# ESP32.net
KiCad netlist of a schematic drawn in Altium Designer
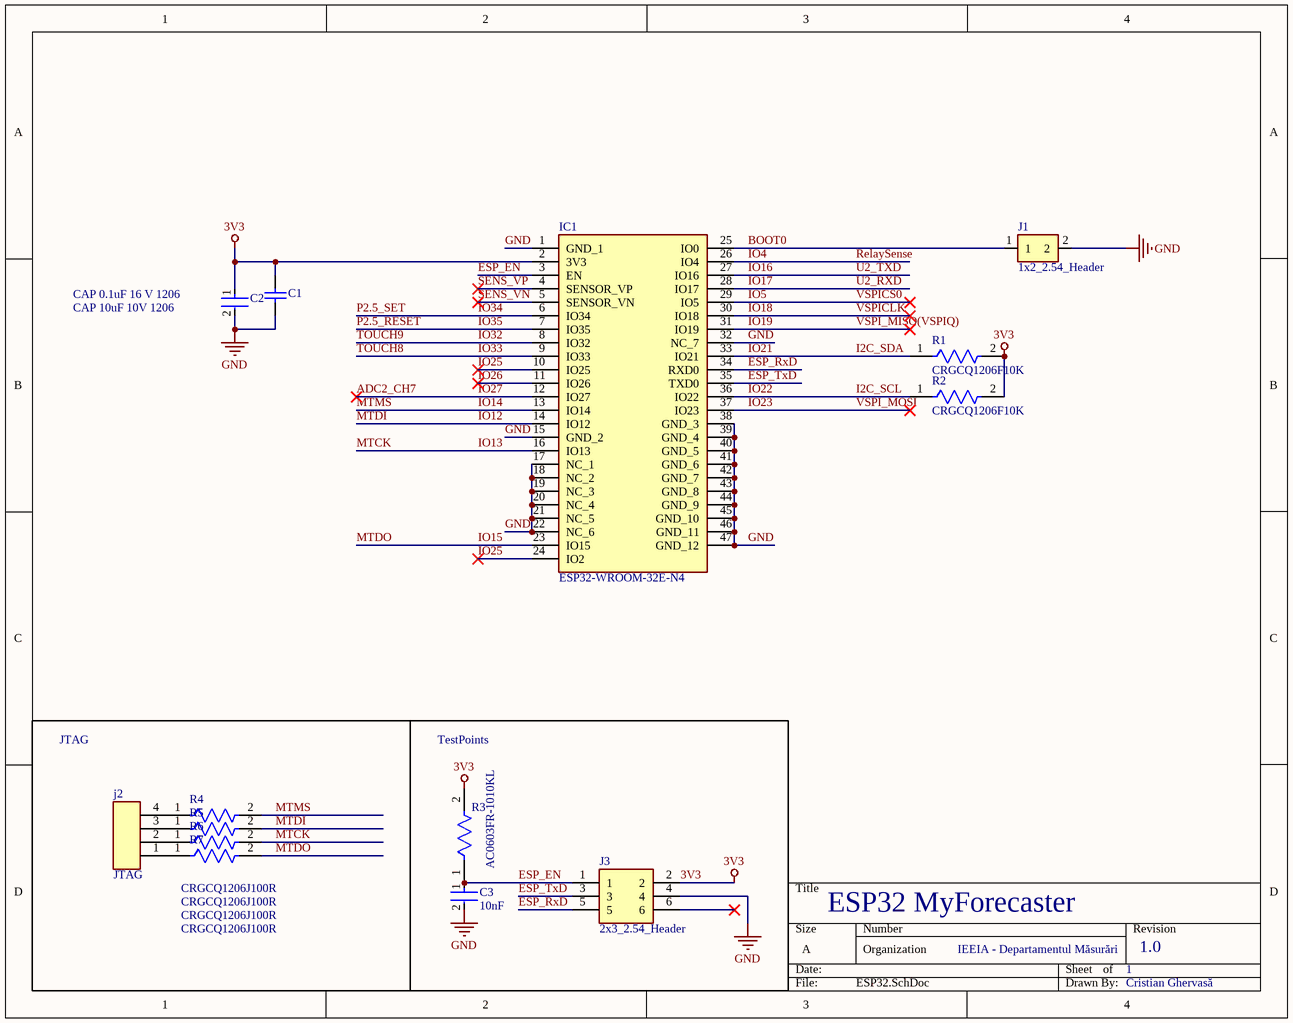
[diagram p0: ESP32.SchDoc]

(export (version "E")
  (design (tool "Eeschema 10.0.6"))
  (components
    (comp (ref "C1")
      (value "CAP 10uF 10V 1206")
      (footprint "CAPC1206(3216)190_N")
      (description "CAP 10uF 10V ±5% 1206 (3216 Metric) Thickness 1.9mm SMD")
      (fields (field (name "TOLERANCE") "Â±5%"))
      (libsource (lib "Altium Content Vault") (part "CAP"))
    )
    (comp (ref "C2")
      (value "CAP 0.1uF 16 V 1206")
      (footprint "FP-C1206C-EB-MFG")
      (description "C1206 0.10 μF X7R 10.00% 16 V")
      (fields (field (name "TOLERANCE") "0.1") (field (name "MANUFACTURER PART NUMBER") "C1206C104K4RACAUTO"))
      (libsource (lib "Altium Content Vault") (part "b4654b650e69147ec39a6b967a45e02"))
    )
    (comp (ref "C3")
      (value "10nF")
      (footprint "FP-CL10-IPC_B")
      (description "Cap Ceramic 10nF 25V X7R ±10% Pad SMD 0603 +125°C T/R")
      (fields (field (name "TOLERANCE") "10%") (field (name "VOLTAGE") "50V"))
      (libsource (lib "Altium Content Vault") (part "b4654b650e69147ec39a6b967a45e02"))
    )
    (comp (ref "IC1")
      (value "ESP32-WROOM-32E-N4")
      (footprint "SamacSys:ESP32WROOM32EN4")
      (description "Integrated Circuit")
      (fields (field (name "MOUSER PART NUMBER") "356-ESP32WRM32E132PH"))
      (libsource (lib "*") (part "ESP32-WROOM-32E-N4"))
    )
    (comp (ref "J1")
      (value "1x2_2.54_Header")
      (footprint "1x2_2.54_Header")
      (description "Connector")
      (libsource (lib "NFC_MedicalAQ") (part "1x2_2.54_Header"))
    )
    (comp (ref "j2")
      (value "JTAG")
      (footprint "1x4_2.54_Header")
      (description "Connector")
      (libsource (lib "NFC_MedicalAQ") (part "1x4_2.54_Header"))
    )
    (comp (ref "J3")
      (value "2x3_2.54_Header")
      (footprint "2x3_2.54_Header")
      (description "Connector")
      (fields
        (field (name "MANUFACTURER_PART_NUMBER") "5-146254-3")
        (field (name "MOUSER PART NUMBER") "571-5-146254-3")
      )
      (libsource (lib "NFC_MedicalAQ") (part "2x3_2.54_Header"))
    )
    (comp (ref "R1")
      (value "CRGCQ1206F10K")
      (footprint "FP-CRGCQ1206-IPC_C")
      (description "CRGCQ1206 10KΩ 0.25W 1% ±100ppm/°C 200V")
      (fields (field (name "MANUFACTURER") "TE Connectivity") (field (name "TOLERANCE") "0.01"))
      (libsource (lib "Altium Content Vault") (part "1029c3af85768c4190bb7ad29bc67b5"))
    )
    (comp (ref "R2")
      (value "CRGCQ1206F10K")
      (footprint "FP-CRGCQ1206-IPC_C")
      (description "CRGCQ1206 10KΩ 0.25W 1% ±100ppm/°C 200V")
      (fields (field (name "MANUFACTURER") "TE Connectivity") (field (name "TOLERANCE") "0.01"))
      (libsource (lib "Altium Content Vault") (part "1029c3af85768c4190bb7ad29bc67b5"))
    )
    (comp (ref "R3")
      (value "AC0603FR-1010KL")
      (footprint "FP-AC0603-IPC_B")
      (description "RES 10KΩ 1.00% 0.1W 0603")
      (fields (field (name "TOLERANCE") "1%"))
      (libsource (lib "Altium Content Vault") (part "1029c3af85768c4190bb7ad29bc67b5"))
    )
    (comp (ref "R4")
      (value "CRGCQ1206J100R")
      (footprint "FP-CRGCQ1206-IPC_C")
      (description "CRGCQ1206 100Ω 0.25W 5% ±200ppm/°C 200V")
      (fields
        (field (name "MANUFACTURER") "TE Connectivity")
        (field (name "OCTOPART") "https://octopart.com/crgcq1206j100r-te+connectivity-91018304")
      )
      (libsource (lib "Altium Content Vault") (part "1029c3af85768c4190bb7ad29bc67b5"))
    )
    (comp (ref "R5")
      (value "CRGCQ1206J100R")
      (footprint "FP-CRGCQ1206-IPC_C")
      (description "CRGCQ1206 100Ω 0.25W 5% ±200ppm/°C 200V")
      (fields
        (field (name "MANUFACTURER") "TE Connectivity")
        (field (name "OCTOPART") "https://octopart.com/crgcq1206j100r-te+connectivity-91018304")
      )
      (libsource (lib "Altium Content Vault") (part "1029c3af85768c4190bb7ad29bc67b5"))
    )
    (comp (ref "R6")
      (value "CRGCQ1206J100R")
      (footprint "FP-CRGCQ1206-IPC_C")
      (description "CRGCQ1206 100Ω 0.25W 5% ±200ppm/°C 200V")
      (fields
        (field (name "MANUFACTURER") "TE Connectivity")
        (field (name "OCTOPART") "https://octopart.com/crgcq1206j100r-te+connectivity-91018304")
      )
      (libsource (lib "Altium Content Vault") (part "1029c3af85768c4190bb7ad29bc67b5"))
    )
    (comp (ref "R7")
      (value "CRGCQ1206J100R")
      (footprint "FP-CRGCQ1206-IPC_C")
      (description "CRGCQ1206 100Ω 0.25W 5% ±200ppm/°C 200V")
      (fields
        (field (name "MANUFACTURER") "TE Connectivity")
        (field (name "OCTOPART") "https://octopart.com/crgcq1206j100r-te+connectivity-91018304")
      )
      (libsource (lib "Altium Content Vault") (part "1029c3af85768c4190bb7ad29bc67b5"))
    )
  )
  (nets
    (net (code "1") (name "/ADC2_CH7") (class "Default")
      (node (ref "IC1") (pin "12") (pinfunction "IO27_12") (pintype "passive+no_connect"))
    )
    (net (code "2") (name "/BOOT0") (class "Default")
      (node (ref "IC1") (pin "25") (pinfunction "IO0_25") (pintype "passive"))
      (node (ref "J1") (pin "1") (pinfunction "1_1") (pintype "passive"))
    )
    (net (code "3") (name "/ESP_EN") (class "Default")
      (node (ref "C3") (pin "1") (pinfunction "1_1") (pintype "passive"))
      (node (ref "IC1") (pin "3") (pinfunction "EN_3") (pintype "passive"))
      (node (ref "J3") (pin "1") (pinfunction "1_1") (pintype "passive"))
      (node (ref "R3") (pin "1") (pinfunction "1_1") (pintype "passive"))
    )
    (net (code "4") (name "/ESP_RxD") (class "Default")
      (node (ref "IC1") (pin "34") (pinfunction "RXD0_34") (pintype "passive"))
      (node (ref "J3") (pin "5") (pinfunction "5_5") (pintype "passive"))
    )
    (net (code "5") (name "/ESP_TxD") (class "Default")
      (node (ref "IC1") (pin "35") (pinfunction "TXD0_35") (pintype "passive"))
      (node (ref "J3") (pin "3") (pinfunction "3_3") (pintype "passive"))
    )
    (net (code "6") (name "/I2C_SCL") (class "Default")
      (node (ref "IC1") (pin "36") (pinfunction "IO22_36") (pintype "passive"))
      (node (ref "R2") (pin "1") (pinfunction "1_1") (pintype "passive"))
    )
    (net (code "7") (name "/I2C_SDA") (class "Default")
      (node (ref "IC1") (pin "33") (pinfunction "IO21_33") (pintype "passive"))
      (node (ref "R1") (pin "1") (pinfunction "1_1") (pintype "passive"))
    )
    (net (code "8") (name "/IO4") (class "Default")
      (node (ref "IC1") (pin "26") (pinfunction "IO4_26") (pintype "passive"))
    )
    (net (code "9") (name "/IO5") (class "Default")
      (node (ref "IC1") (pin "29") (pinfunction "IO5_29") (pintype "passive+no_connect"))
    )
    (net (code "10") (name "/IO12") (class "Default")
      (node (ref "IC1") (pin "14") (pinfunction "IO12_14") (pintype "passive"))
      (node (ref "R5") (pin "2") (pinfunction "2_2") (pintype "passive"))
    )
    (net (code "11") (name "/IO13") (class "Default")
      (node (ref "IC1") (pin "16") (pinfunction "IO13_16") (pintype "passive"))
      (node (ref "R6") (pin "2") (pinfunction "2_2") (pintype "passive"))
    )
    (net (code "12") (name "/IO14") (class "Default")
      (node (ref "IC1") (pin "13") (pinfunction "IO14_13") (pintype "passive"))
      (node (ref "R4") (pin "2") (pinfunction "2_2") (pintype "passive"))
    )
    (net (code "13") (name "/IO15") (class "Default")
      (node (ref "IC1") (pin "23") (pinfunction "IO15_23") (pintype "passive"))
      (node (ref "R7") (pin "2") (pinfunction "2_2") (pintype "passive"))
    )
    (net (code "14") (name "/IO16") (class "Default")
      (node (ref "IC1") (pin "27") (pinfunction "IO16_27") (pintype "passive"))
    )
    (net (code "15") (name "/IO17") (class "Default")
      (node (ref "IC1") (pin "28") (pinfunction "IO17_28") (pintype "passive"))
    )
    (net (code "16") (name "/IO18") (class "Default")
      (node (ref "IC1") (pin "30") (pinfunction "IO18_30") (pintype "passive+no_connect"))
    )
    (net (code "17") (name "/IO19") (class "Default")
      (node (ref "IC1") (pin "31") (pinfunction "IO19_31") (pintype "passive+no_connect"))
    )
    (net (code "18") (name "/IO23") (class "Default")
      (node (ref "IC1") (pin "37") (pinfunction "IO23_37") (pintype "passive+no_connect"))
    )
    (net (code "19") (name "/IO25") (class "Default")
      (node (ref "IC1") (pin "10") (pinfunction "IO25_10") (pintype "passive"))
      (node (ref "IC1") (pin "24") (pinfunction "IO2_24") (pintype "passive"))
    )
    (net (code "20") (name "/IO26") (class "Default")
      (node (ref "IC1") (pin "11") (pinfunction "IO26_11") (pintype "passive+no_connect"))
    )
    (net (code "21") (name "/IO32") (class "Default")
      (node (ref "IC1") (pin "8") (pinfunction "IO32_8") (pintype "passive"))
    )
    (net (code "22") (name "/IO33") (class "Default")
      (node (ref "IC1") (pin "9") (pinfunction "IO33_9") (pintype "passive"))
    )
    (net (code "23") (name "/IO34") (class "Default")
      (node (ref "IC1") (pin "6") (pinfunction "IO34_6") (pintype "passive"))
    )
    (net (code "24") (name "/IO35") (class "Default")
      (node (ref "IC1") (pin "7") (pinfunction "IO35_7") (pintype "passive"))
    )
    (net (code "25") (name "/SENS_VN") (class "Default")
      (node (ref "IC1") (pin "5") (pinfunction "SENSOR_VN_5") (pintype "passive+no_connect"))
    )
    (net (code "26") (name "/SENS_VP") (class "Default")
      (node (ref "IC1") (pin "4") (pinfunction "SENSOR_VP_4") (pintype "passive+no_connect"))
    )
    (net (code "27") (name "3V3") (class "Default")
      (node (ref "C1") (pin "2") (pinfunction "2_2") (pintype "passive"))
      (node (ref "C2") (pin "1") (pinfunction "1_1") (pintype "passive"))
      (node (ref "IC1") (pin "2") (pinfunction "3V3_2") (pintype "passive"))
      (node (ref "J3") (pin "2") (pinfunction "2_2") (pintype "passive"))
      (node (ref "R1") (pin "2") (pinfunction "2_2") (pintype "passive"))
      (node (ref "R2") (pin "2") (pinfunction "2_2") (pintype "passive"))
      (node (ref "R3") (pin "2") (pinfunction "2_2") (pintype "passive"))
    )
    (net (code "28") (name "GND") (class "Default")
      (node (ref "C1") (pin "1") (pinfunction "1_1") (pintype "passive"))
      (node (ref "C2") (pin "2") (pinfunction "2_2") (pintype "passive"))
      (node (ref "C3") (pin "2") (pinfunction "2_2") (pintype "passive"))
      (node (ref "IC1") (pin "1") (pinfunction "GND_1_1") (pintype "passive"))
      (node (ref "IC1") (pin "15") (pinfunction "GND_2_15") (pintype "passive"))
      (node (ref "IC1") (pin "17") (pinfunction "NC_1_17") (pintype "passive"))
      (node (ref "IC1") (pin "18") (pinfunction "NC_2_18") (pintype "passive"))
      (node (ref "IC1") (pin "19") (pinfunction "NC_3_19") (pintype "passive"))
      (node (ref "IC1") (pin "20") (pinfunction "NC_4_20") (pintype "passive"))
      (node (ref "IC1") (pin "21") (pinfunction "NC_5_21") (pintype "passive"))
      (node (ref "IC1") (pin "22") (pinfunction "NC_6_22") (pintype "passive"))
      (node (ref "IC1") (pin "32") (pinfunction "NC_7_32") (pintype "passive"))
      (node (ref "IC1") (pin "38") (pinfunction "GND_3_38") (pintype "passive"))
      (node (ref "IC1") (pin "39") (pinfunction "GND_4_39") (pintype "passive"))
      (node (ref "IC1") (pin "40") (pinfunction "GND_5_40") (pintype "passive"))
      (node (ref "IC1") (pin "41") (pinfunction "GND_6_41") (pintype "passive"))
      (node (ref "IC1") (pin "42") (pinfunction "GND_7_42") (pintype "passive"))
      (node (ref "IC1") (pin "43") (pinfunction "GND_8_43") (pintype "passive"))
      (node (ref "IC1") (pin "44") (pinfunction "GND_9_44") (pintype "passive"))
      (node (ref "IC1") (pin "45") (pinfunction "GND_10_45") (pintype "passive"))
      (node (ref "IC1") (pin "46") (pinfunction "GND_11_46") (pintype "passive"))
      (node (ref "IC1") (pin "47") (pinfunction "GND_12_47") (pintype "passive"))
      (node (ref "J1") (pin "2") (pinfunction "2_2") (pintype "passive"))
      (node (ref "J3") (pin "4") (pinfunction "4_4") (pintype "passive"))
    )
    (net (code "29") (name "Net-(R4-Pad1)") (class "Default")
      (node (ref "R4") (pin "1") (pinfunction "1_1") (pintype "passive"))
      (node (ref "j2") (pin "4") (pintype "passive"))
    )
    (net (code "30") (name "Net-(R5-Pad1)") (class "Default")
      (node (ref "R5") (pin "1") (pinfunction "1_1") (pintype "passive"))
      (node (ref "j2") (pin "3") (pintype "passive"))
    )
    (net (code "31") (name "Net-(R6-Pad1)") (class "Default")
      (node (ref "R6") (pin "1") (pinfunction "1_1") (pintype "passive"))
      (node (ref "j2") (pin "2") (pintype "passive"))
    )
    (net (code "32") (name "Net-(R7-Pad1)") (class "Default")
      (node (ref "R7") (pin "1") (pinfunction "1_1") (pintype "passive"))
      (node (ref "j2") (pin "1") (pintype "passive"))
    )
    (net (code "33") (name "unconnected-(J3-Pad6)") (class "Default")
      (node (ref "J3") (pin "6") (pinfunction "6_6") (pintype "passive+no_connect"))
    )
  )
)
